# Tesla_v0_1.net
KiCad netlist of a schematic drawn in EAGLE
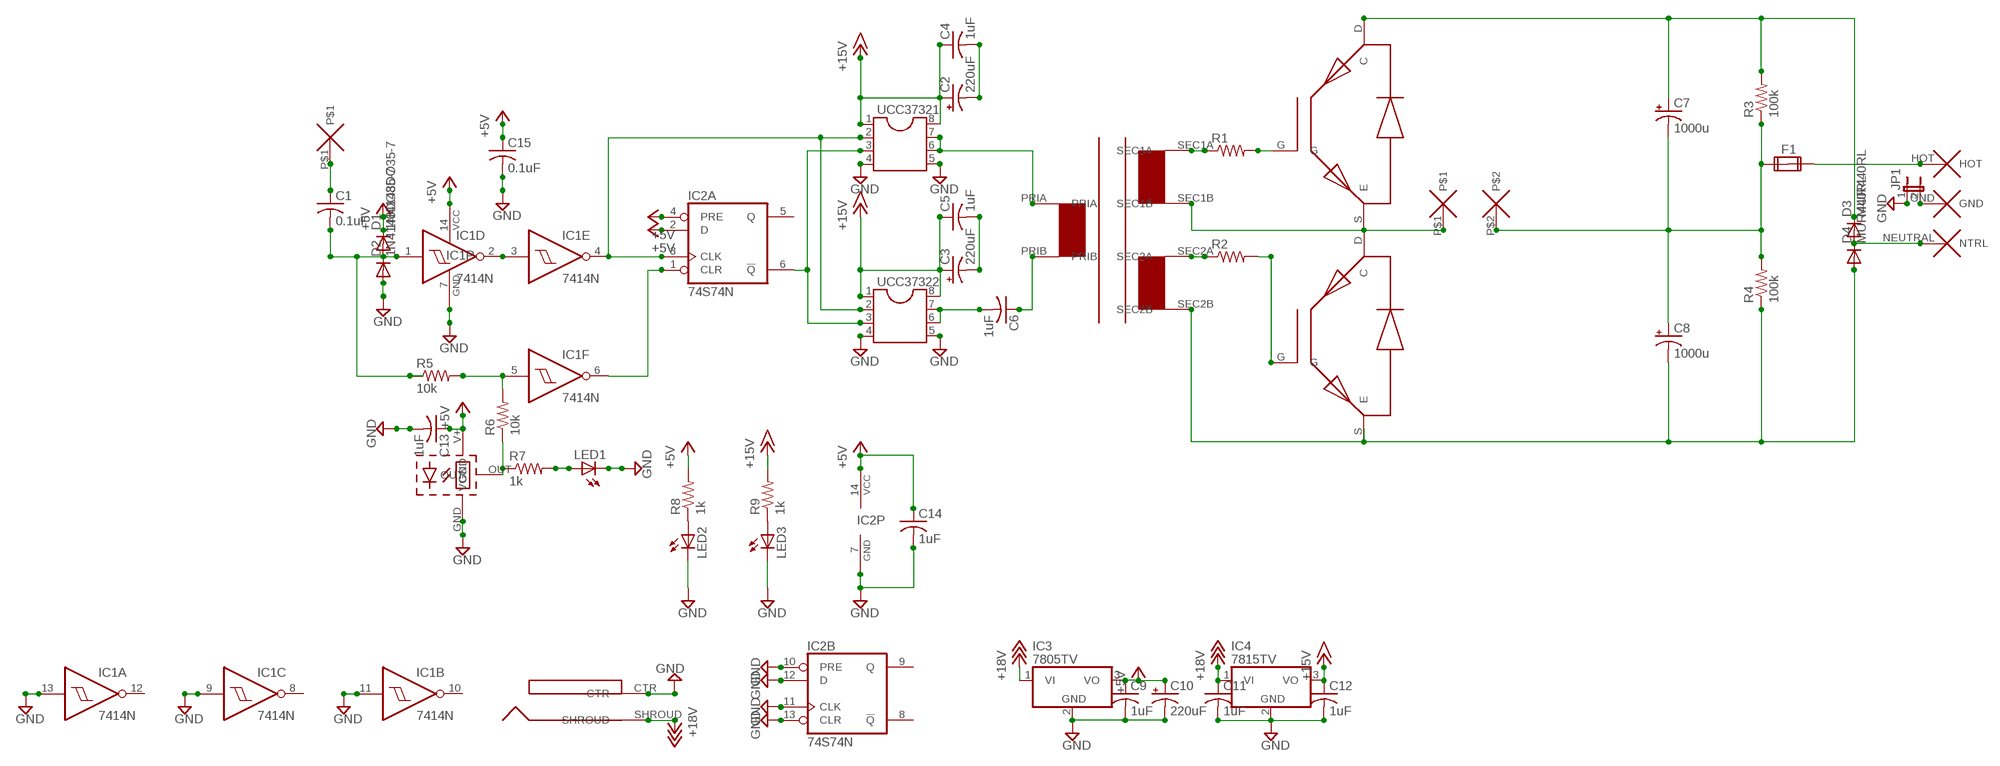
[diagram p0: schematic, sheet 1]

(export (version "E")
  (design (tool "Eeschema 10.0.6"))
  (components
    (comp (ref "C1")
      (value "0.1uF")
      (footprint "eagle-import:C050-024X044")
      (libsource (lib "eagle-import") (part "C-US050-024X044"))
    )
    (comp (ref "C2")
      (value "220uF")
      (footprint "eagle-import:E5-10,5")
      (libsource (lib "eagle-import") (part "CPOL-USE5-10.5"))
    )
    (comp (ref "C3")
      (value "220uF")
      (footprint "eagle-import:E5-10,5")
      (libsource (lib "eagle-import") (part "CPOL-USE5-10.5"))
    )
    (comp (ref "C4")
      (value "1uF")
      (footprint "eagle-import:C050-024X044")
      (libsource (lib "eagle-import") (part "C-US050-024X044"))
    )
    (comp (ref "C5")
      (value "1uF")
      (footprint "eagle-import:C050-024X044")
      (libsource (lib "eagle-import") (part "C-US050-024X044"))
    )
    (comp (ref "C6")
      (value "1uF")
      (footprint "eagle-import:C050-024X044")
      (libsource (lib "eagle-import") (part "C-US050-024X044"))
    )
    (comp (ref "C7")
      (value "1000u")
      (footprint "eagle-import:EB25D")
      (libsource (lib "eagle-import") (part "CPOL-USE10-25"))
    )
    (comp (ref "C8")
      (value "1000u")
      (footprint "eagle-import:EB25D")
      (libsource (lib "eagle-import") (part "CPOL-USE10-25"))
    )
    (comp (ref "C9")
      (value "1uF")
      (footprint "eagle-import:C050-024X044")
      (libsource (lib "eagle-import") (part "C-US050-024X044"))
    )
    (comp (ref "C10")
      (value "220uF")
      (footprint "eagle-import:E5-10,5")
      (libsource (lib "eagle-import") (part "CPOL-USE5-10.5"))
    )
    (comp (ref "C11")
      (value "1uF")
      (footprint "eagle-import:C050-024X044")
      (libsource (lib "eagle-import") (part "C-US050-024X044"))
    )
    (comp (ref "C12")
      (value "1uF")
      (footprint "eagle-import:C050-024X044")
      (libsource (lib "eagle-import") (part "C-US050-024X044"))
    )
    (comp (ref "C13")
      (value "1uF")
      (footprint "eagle-import:C050-024X044")
      (libsource (lib "eagle-import") (part "C-US050-024X044"))
    )
    (comp (ref "C14")
      (value "1uF")
      (footprint "eagle-import:C050-024X044")
      (libsource (lib "eagle-import") (part "C-US050-024X044"))
    )
    (comp (ref "C15")
      (value "0.1uF")
      (footprint "eagle-import:C050-024X044")
      (libsource (lib "eagle-import") (part "C-US050-024X044"))
    )
    (comp (ref "D1")
      (value "1N4148DO35-7")
      (footprint "eagle-import:DO35-7")
      (libsource (lib "eagle-import") (part "1N4148DO35-7"))
    )
    (comp (ref "D2")
      (value "1N4148DO35-7")
      (footprint "eagle-import:DO35-7")
      (libsource (lib "eagle-import") (part "1N4148DO35-7"))
    )
    (comp (ref "D3")
      (value "MUR440RL")
      (footprint "eagle-import:C2673")
      (libsource (lib "eagle-import") (part "MUR440RL"))
    )
    (comp (ref "D4")
      (value "MUR440RL")
      (footprint "eagle-import:C2673")
      (libsource (lib "eagle-import") (part "MUR440RL"))
    )
    (comp (ref "F1")
      (value "FUSE2P")
      (footprint "eagle-import:FUSE1")
      (libsource (lib "eagle-import") (part "FUSE2P"))
    )
    (comp (ref "IC1")
      (value "7414N")
      (footprint "eagle-import:DIL14")
      (libsource (lib "eagle-import") (part "7414N"))
    )
    (comp (ref "IC2")
      (value "74S74N")
      (footprint "eagle-import:DIL14")
      (libsource (lib "eagle-import") (part "7474NS"))
    )
    (comp (ref "IC3")
      (value "7805TV")
      (footprint "eagle-import:TO220V")
      (libsource (lib "eagle-import") (part "78TV05"))
    )
    (comp (ref "IC4")
      (value "7815TV")
      (footprint "eagle-import:TO220V")
      (libsource (lib "eagle-import") (part "78TV15"))
    )
    (comp (ref "JP1")
      (value "JP1E")
      (footprint "eagle-import:JP1")
      (libsource (lib "eagle-import") (part "JP1E"))
    )
    (comp (ref "LED1")
      (value "LED5MM")
      (footprint "eagle-import:LED5MM")
      (libsource (lib "eagle-import") (part "LED5MM"))
    )
    (comp (ref "LED2")
      (value "LED5MM")
      (footprint "eagle-import:LED5MM")
      (libsource (lib "eagle-import") (part "LED5MM"))
    )
    (comp (ref "LED3")
      (value "LED5MM")
      (footprint "eagle-import:LED5MM")
      (libsource (lib "eagle-import") (part "LED5MM"))
    )
    (comp (ref "R1")
      (value "R-US_0309/V")
      (footprint "eagle-import:0309V")
      (libsource (lib "eagle-import") (part "R-US_0309/V"))
    )
    (comp (ref "R2")
      (value "R-US_0309/V")
      (footprint "eagle-import:0309V")
      (libsource (lib "eagle-import") (part "R-US_0309/V"))
    )
    (comp (ref "R3")
      (value "100k")
      (footprint "eagle-import:0309_10")
      (libsource (lib "eagle-import") (part "R-US_0309/10"))
    )
    (comp (ref "R4")
      (value "100k")
      (footprint "eagle-import:0309_10")
      (libsource (lib "eagle-import") (part "R-US_0309/10"))
    )
    (comp (ref "R5")
      (value "10k")
      (footprint "eagle-import:0207_7")
      (libsource (lib "eagle-import") (part "R-US_0207/7"))
    )
    (comp (ref "R6")
      (value "10k")
      (footprint "eagle-import:0207_7")
      (libsource (lib "eagle-import") (part "R-US_0207/7"))
    )
    (comp (ref "R7")
      (value "1k")
      (footprint "eagle-import:0207_7")
      (libsource (lib "eagle-import") (part "R-US_0207/7"))
    )
    (comp (ref "R8")
      (value "1k")
      (footprint "eagle-import:0207_7")
      (libsource (lib "eagle-import") (part "R-US_0207/7"))
    )
    (comp (ref "R9")
      (value "1k")
      (footprint "eagle-import:0207_7")
      (libsource (lib "eagle-import") (part "R-US_0207/7"))
    )
    (comp (ref "U$1")
      (value "PJ-037B")
      (footprint "eagle-import:DJC0202")
      (libsource (lib "eagle-import") (part "PJ-037B"))
    )
    (comp (ref "U$2")
      (value "12AWG_PAD")
      (footprint "eagle-import:12AWG_PAD")
      (libsource (lib "eagle-import") (part "12AWG_PAD"))
    )
    (comp (ref "U$3")
      (value "GDT")
      (footprint "eagle-import:GDT")
      (libsource (lib "eagle-import") (part "GDT"))
    )
    (comp (ref "U$4")
      (value "FGH40N60SMD")
      (footprint "eagle-import:TO247BV")
      (libsource (lib "eagle-import") (part "FGH40N60SMD"))
    )
    (comp (ref "U$5")
      (value "FGH40N60SMD")
      (footprint "eagle-import:TO247BV")
      (libsource (lib "eagle-import") (part "FGH40N60SMD"))
    )
    (comp (ref "U$6")
      (value "2TERMINAL")
      (footprint "eagle-import:2TERMINAL")
      (libsource (lib "eagle-import") (part "2TERMINAL"))
    )
    (comp (ref "U$7")
      (value "IEC")
      (footprint "eagle-import:IECPORT")
      (libsource (lib "eagle-import") (part "IEC"))
    )
    (comp (ref "U$8")
      (value "IF-D95")
      (footprint "eagle-import:IFD95")
      (libsource (lib "eagle-import") (part "IF-D95"))
    )
    (comp (ref "UCC37321")
      (value "DIL8")
      (footprint "eagle-import:DIL08")
      (libsource (lib "eagle-import") (part "DIL8"))
    )
    (comp (ref "UCC37322")
      (value "DIL8")
      (footprint "eagle-import:DIL08")
      (libsource (lib "eagle-import") (part "DIL8"))
    )
  )
  (nets
    (net (code "1") (name "+5V") (class "Default")
      (node (ref "C10") (pin "+") (pinfunction "+_+") (pintype "passive"))
      (node (ref "C13") (pin "1") (pinfunction "1_1") (pintype "passive"))
      (node (ref "C14") (pin "1") (pinfunction "1_1") (pintype "passive"))
      (node (ref "C15") (pin "1") (pinfunction "1_1") (pintype "passive"))
      (node (ref "C9") (pin "1") (pinfunction "1_1") (pintype "passive"))
      (node (ref "D1") (pin "C") (pinfunction "C_C") (pintype "passive"))
      (node (ref "IC1") (pin "14") (pinfunction "VCC_14") (pintype "power_in"))
      (node (ref "IC2") (pin "14") (pinfunction "VCC_14") (pintype "power_in"))
      (node (ref "IC2") (pin "2") (pinfunction "D_2") (pintype "input"))
      (node (ref "IC2") (pin "4") (pinfunction "PRE_4") (pintype "input"))
      (node (ref "IC3") (pin "3") (pinfunction "VO_3") (pintype "passive"))
      (node (ref "R8") (pin "2") (pinfunction "2_2") (pintype "passive"))
      (node (ref "U$8") (pin "V+") (pinfunction "VCC_V+") (pintype "bidirectional"))
    )
    (net (code "2") (name "+15V") (class "Default")
      (node (ref "C12") (pin "1") (pinfunction "1_1") (pintype "passive"))
      (node (ref "C2") (pin "+") (pinfunction "+_+") (pintype "passive"))
      (node (ref "C3") (pin "+") (pinfunction "+_+") (pintype "passive"))
      (node (ref "C4") (pin "1") (pinfunction "1_1") (pintype "passive"))
      (node (ref "C5") (pin "1") (pinfunction "1_1") (pintype "passive"))
      (node (ref "IC4") (pin "3") (pinfunction "VO_3") (pintype "passive"))
      (node (ref "R9") (pin "2") (pinfunction "2_2") (pintype "passive"))
      (node (ref "UCC37321") (pin "1") (pinfunction "1_1") (pintype "passive"))
      (node (ref "UCC37321") (pin "8") (pinfunction "8_8") (pintype "passive"))
      (node (ref "UCC37322") (pin "1") (pinfunction "1_1") (pintype "passive"))
      (node (ref "UCC37322") (pin "8") (pinfunction "8_8") (pintype "passive"))
    )
    (net (code "3") (name "+18V") (class "Default")
      (node (ref "C11") (pin "1") (pinfunction "1_1") (pintype "passive"))
      (node (ref "IC3") (pin "1") (pinfunction "VI_1") (pintype "input"))
      (node (ref "IC4") (pin "1") (pinfunction "VI_1") (pintype "input"))
      (node (ref "U$1") (pin "SHROUD") (pinfunction "SHROUD_SHROUD") (pintype "bidirectional"))
    )
    (net (code "4") (name "GND") (class "Default")
      (node (ref "C10") (pin "-") (pinfunction "-_-") (pintype "passive"))
      (node (ref "C11") (pin "2") (pinfunction "2_2") (pintype "passive"))
      (node (ref "C12") (pin "2") (pinfunction "2_2") (pintype "passive"))
      (node (ref "C13") (pin "2") (pinfunction "2_2") (pintype "passive"))
      (node (ref "C14") (pin "2") (pinfunction "2_2") (pintype "passive"))
      (node (ref "C15") (pin "2") (pinfunction "2_2") (pintype "passive"))
      (node (ref "C9") (pin "2") (pinfunction "2_2") (pintype "passive"))
      (node (ref "D2") (pin "A") (pinfunction "A_A") (pintype "passive"))
      (node (ref "IC1") (pin "11") (pinfunction "I_11") (pintype "input"))
      (node (ref "IC1") (pin "13") (pinfunction "I_13") (pintype "input"))
      (node (ref "IC1") (pin "7") (pinfunction "GND_7") (pintype "power_in"))
      (node (ref "IC1") (pin "9") (pinfunction "I_9") (pintype "input"))
      (node (ref "IC2") (pin "10") (pinfunction "PRE_10") (pintype "input"))
      (node (ref "IC2") (pin "11") (pinfunction "CLK_11") (pintype "input"))
      (node (ref "IC2") (pin "12") (pinfunction "D_12") (pintype "input"))
      (node (ref "IC2") (pin "13") (pinfunction "CLR_13") (pintype "input"))
      (node (ref "IC2") (pin "7") (pinfunction "GND_7") (pintype "power_in"))
      (node (ref "IC3") (pin "2") (pinfunction "GND_2") (pintype "passive"))
      (node (ref "IC4") (pin "2") (pinfunction "GND_2") (pintype "passive"))
      (node (ref "JP1") (pin "1") (pinfunction "1_1") (pintype "passive"))
      (node (ref "LED1") (pin "K") (pinfunction "C_K") (pintype "passive"))
      (node (ref "LED2") (pin "K") (pinfunction "C_K") (pintype "passive"))
      (node (ref "LED3") (pin "K") (pinfunction "C_K") (pintype "passive"))
      (node (ref "U$1") (pin "CTR") (pinfunction "CTR_CTR") (pintype "bidirectional"))
      (node (ref "U$8") (pin "GND") (pinfunction "GND_GND") (pintype "bidirectional"))
      (node (ref "UCC37321") (pin "4") (pinfunction "4_4") (pintype "passive"))
      (node (ref "UCC37321") (pin "5") (pinfunction "5_5") (pintype "passive"))
      (node (ref "UCC37322") (pin "4") (pinfunction "4_4") (pintype "passive"))
      (node (ref "UCC37322") (pin "5") (pinfunction "5_5") (pintype "passive"))
    )
    (net (code "5") (name "Net-(C1-Pad1)") (class "Default")
      (node (ref "C1") (pin "1") (pinfunction "1_1") (pintype "passive"))
      (node (ref "U$2") (pin "P$1") (pinfunction "P$1_P$1") (pintype "bidirectional"))
    )
    (net (code "6") (name "Net-(C2-Pad-)") (class "Default")
      (node (ref "C2") (pin "-") (pinfunction "-_-") (pintype "passive"))
      (node (ref "C4") (pin "2") (pinfunction "2_2") (pintype "passive"))
    )
    (net (code "7") (name "Net-(C3-Pad-)") (class "Default")
      (node (ref "C3") (pin "-") (pinfunction "-_-") (pintype "passive"))
      (node (ref "C5") (pin "2") (pinfunction "2_2") (pintype "passive"))
    )
    (net (code "8") (name "Net-(C6-Pad1)") (class "Default")
      (node (ref "C6") (pin "1") (pinfunction "1_1") (pintype "passive"))
      (node (ref "U$3") (pin "PRIB") (pinfunction "PRIB_PRIB") (pintype "input"))
    )
    (net (code "9") (name "Net-(C6-Pad2)") (class "Default")
      (node (ref "C6") (pin "2") (pinfunction "2_2") (pintype "passive"))
      (node (ref "UCC37322") (pin "6") (pinfunction "6_6") (pintype "passive"))
      (node (ref "UCC37322") (pin "7") (pinfunction "7_7") (pintype "passive"))
    )
    (net (code "10") (name "Net-(C7-Pad-)") (class "Default")
      (node (ref "C7") (pin "-") (pinfunction "-_-") (pintype "passive"))
      (node (ref "C8") (pin "+") (pinfunction "+_+") (pintype "passive"))
      (node (ref "F1") (pin "1A") (pinfunction "1A_1A") (pintype "passive"))
      (node (ref "R3") (pin "1") (pinfunction "1_1") (pintype "passive"))
      (node (ref "R4") (pin "2") (pinfunction "2_2") (pintype "passive"))
      (node (ref "U$6") (pin "P$2") (pinfunction "P$2_P$2") (pintype "bidirectional"))
    )
    (net (code "11") (name "Net-(F1-Pad2A)") (class "Default")
      (node (ref "F1") (pin "2A") (pinfunction "2A_2A") (pintype "passive"))
      (node (ref "U$7") (pin "HOT") (pinfunction "HOT_HOT") (pintype "bidirectional"))
    )
    (net (code "12") (name "Net-(IC1D-I)") (class "Default")
      (node (ref "C1") (pin "2") (pinfunction "2_2") (pintype "passive"))
      (node (ref "D1") (pin "A") (pinfunction "A_A") (pintype "passive"))
      (node (ref "D2") (pin "C") (pinfunction "C_C") (pintype "passive"))
      (node (ref "IC1") (pin "1") (pinfunction "I_1") (pintype "input"))
      (node (ref "R5") (pin "1") (pinfunction "1_1") (pintype "passive"))
    )
    (net (code "13") (name "Net-(IC1D-O)") (class "Default")
      (node (ref "IC1") (pin "2") (pinfunction "O_2") (pintype "output"))
      (node (ref "IC1") (pin "3") (pinfunction "I_3") (pintype "input"))
    )
    (net (code "14") (name "Net-(IC1E-O)") (class "Default")
      (node (ref "IC1") (pin "4") (pinfunction "O_4") (pintype "output"))
      (node (ref "IC2") (pin "3") (pinfunction "CLK_3") (pintype "input"))
      (node (ref "UCC37321") (pin "2") (pinfunction "2_2") (pintype "passive"))
      (node (ref "UCC37322") (pin "2") (pinfunction "2_2") (pintype "passive"))
    )
    (net (code "15") (name "Net-(IC1F-I)") (class "Default")
      (node (ref "IC1") (pin "5") (pinfunction "I_5") (pintype "input"))
      (node (ref "R5") (pin "2") (pinfunction "2_2") (pintype "passive"))
      (node (ref "R6") (pin "2") (pinfunction "2_2") (pintype "passive"))
    )
    (net (code "16") (name "Net-(IC1F-O)") (class "Default")
      (node (ref "IC1") (pin "6") (pinfunction "O_6") (pintype "output"))
      (node (ref "IC2") (pin "1") (pinfunction "CLR_1") (pintype "input"))
    )
    (net (code "17") (name "Net-(IC2A-~{Q})") (class "Default")
      (node (ref "IC2") (pin "6") (pinfunction "~{Q}_6") (pintype "output"))
      (node (ref "UCC37321") (pin "3") (pinfunction "3_3") (pintype "passive"))
      (node (ref "UCC37322") (pin "3") (pinfunction "3_3") (pintype "passive"))
    )
    (net (code "18") (name "Net-(JP1-Pad2)") (class "Default")
      (node (ref "JP1") (pin "2") (pinfunction "2_2") (pintype "passive"))
      (node (ref "U$7") (pin "GND") (pinfunction "GND_GND") (pintype "bidirectional"))
    )
    (net (code "19") (name "Net-(LED1-PadA)") (class "Default")
      (node (ref "LED1") (pin "A") (pinfunction "A_A") (pintype "passive"))
      (node (ref "R7") (pin "2") (pinfunction "2_2") (pintype "passive"))
    )
    (net (code "20") (name "Net-(LED2-PadA)") (class "Default")
      (node (ref "LED2") (pin "A") (pinfunction "A_A") (pintype "passive"))
      (node (ref "R8") (pin "1") (pinfunction "1_1") (pintype "passive"))
    )
    (net (code "21") (name "Net-(LED3-PadA)") (class "Default")
      (node (ref "LED3") (pin "A") (pinfunction "A_A") (pintype "passive"))
      (node (ref "R9") (pin "1") (pinfunction "1_1") (pintype "passive"))
    )
    (net (code "22") (name "Net-(R1-Pad1)") (class "Default")
      (node (ref "R1") (pin "1") (pinfunction "1_1") (pintype "passive"))
      (node (ref "U$3") (pin "SEC1A") (pinfunction "SEC1A_SEC1A") (pintype "output"))
    )
    (net (code "23") (name "Net-(R1-Pad2)") (class "Default")
      (node (ref "R1") (pin "2") (pinfunction "2_2") (pintype "passive"))
      (node (ref "U$4") (pin "G") (pinfunction "G_G") (pintype "bidirectional"))
    )
    (net (code "24") (name "Net-(R2-Pad1)") (class "Default")
      (node (ref "R2") (pin "1") (pinfunction "1_1") (pintype "passive"))
      (node (ref "U$3") (pin "SEC2A") (pinfunction "SEC2A_SEC2A") (pintype "output"))
    )
    (net (code "25") (name "Net-(R2-Pad2)") (class "Default")
      (node (ref "R2") (pin "2") (pinfunction "2_2") (pintype "passive"))
      (node (ref "U$5") (pin "G") (pinfunction "G_G") (pintype "bidirectional"))
    )
    (net (code "26") (name "Net-(R6-Pad1)") (class "Default")
      (node (ref "R6") (pin "1") (pinfunction "1_1") (pintype "passive"))
      (node (ref "R7") (pin "1") (pinfunction "1_1") (pintype "passive"))
      (node (ref "U$8") (pin "OUT") (pinfunction "OUT_OUT") (pintype "bidirectional"))
    )
    (net (code "27") (name "Net-(U$3-PadPRIA)") (class "Default")
      (node (ref "U$3") (pin "PRIA") (pinfunction "PRIA_PRIA") (pintype "input"))
      (node (ref "UCC37321") (pin "6") (pinfunction "6_6") (pintype "passive"))
      (node (ref "UCC37321") (pin "7") (pinfunction "7_7") (pintype "passive"))
    )
    (net (code "28") (name "Net-(U$4-C)") (class "Default")
      (node (ref "C7") (pin "+") (pinfunction "+_+") (pintype "passive"))
      (node (ref "D3") (pin "C") (pinfunction "C_C") (pintype "passive"))
      (node (ref "R3") (pin "2") (pinfunction "2_2") (pintype "passive"))
      (node (ref "U$4") (pin "D") (pinfunction "C_D") (pintype "bidirectional"))
    )
    (net (code "29") (name "Net-(U$4-E)") (class "Default")
      (node (ref "U$3") (pin "SEC1B") (pinfunction "SEC1B_SEC1B") (pintype "output"))
      (node (ref "U$4") (pin "S") (pinfunction "E_S") (pintype "bidirectional"))
      (node (ref "U$5") (pin "D") (pinfunction "C_D") (pintype "bidirectional"))
      (node (ref "U$6") (pin "P$1") (pinfunction "P$1_P$1") (pintype "bidirectional"))
    )
    (net (code "30") (name "Net-(U$5-E)") (class "Default")
      (node (ref "C8") (pin "-") (pinfunction "-_-") (pintype "passive"))
      (node (ref "D4") (pin "A") (pinfunction "A_A") (pintype "passive"))
      (node (ref "R4") (pin "1") (pinfunction "1_1") (pintype "passive"))
      (node (ref "U$3") (pin "SEC2B") (pinfunction "SEC2B_SEC2B") (pintype "output"))
      (node (ref "U$5") (pin "S") (pinfunction "E_S") (pintype "bidirectional"))
    )
    (net (code "31") (name "Net-(U$7-NTRL)") (class "Default")
      (node (ref "D3") (pin "A") (pinfunction "A_A") (pintype "passive"))
      (node (ref "D4") (pin "C") (pinfunction "C_C") (pintype "passive"))
      (node (ref "U$7") (pin "NEUTRAL") (pinfunction "NTRL_NEUTRAL") (pintype "bidirectional"))
    )
    (net (code "32") (name "unconnected-(F1-Pad1B)") (class "Default")
      (node (ref "F1") (pin "1B") (pinfunction "1B_1B") (pintype "passive"))
    )
    (net (code "33") (name "unconnected-(F1-Pad2B)") (class "Default")
      (node (ref "F1") (pin "2B") (pinfunction "2B_2B") (pintype "passive"))
    )
    (net (code "34") (name "unconnected-(IC1A-O-Pad12)") (class "Default")
      (node (ref "IC1") (pin "12") (pinfunction "O_12") (pintype "output"))
    )
    (net (code "35") (name "unconnected-(IC1B-O-Pad10)") (class "Default")
      (node (ref "IC1") (pin "10") (pinfunction "O_10") (pintype "output"))
    )
    (net (code "36") (name "unconnected-(IC1C-O-Pad8)") (class "Default")
      (node (ref "IC1") (pin "8") (pinfunction "O_8") (pintype "output"))
    )
    (net (code "37") (name "unconnected-(IC2A-Q-Pad5)") (class "Default")
      (node (ref "IC2") (pin "5") (pinfunction "Q_5") (pintype "output"))
    )
    (net (code "38") (name "unconnected-(IC2B-Q-Pad9)") (class "Default")
      (node (ref "IC2") (pin "9") (pinfunction "Q_9") (pintype "output"))
    )
    (net (code "39") (name "unconnected-(IC2B-~{Q}-Pad8)") (class "Default")
      (node (ref "IC2") (pin "8") (pinfunction "~{Q}_8") (pintype "output"))
    )
  )
)
